# STM8L-FOX_80m_CNTL_V5_3.net
KiCad netlist of a schematic drawn in EAGLE
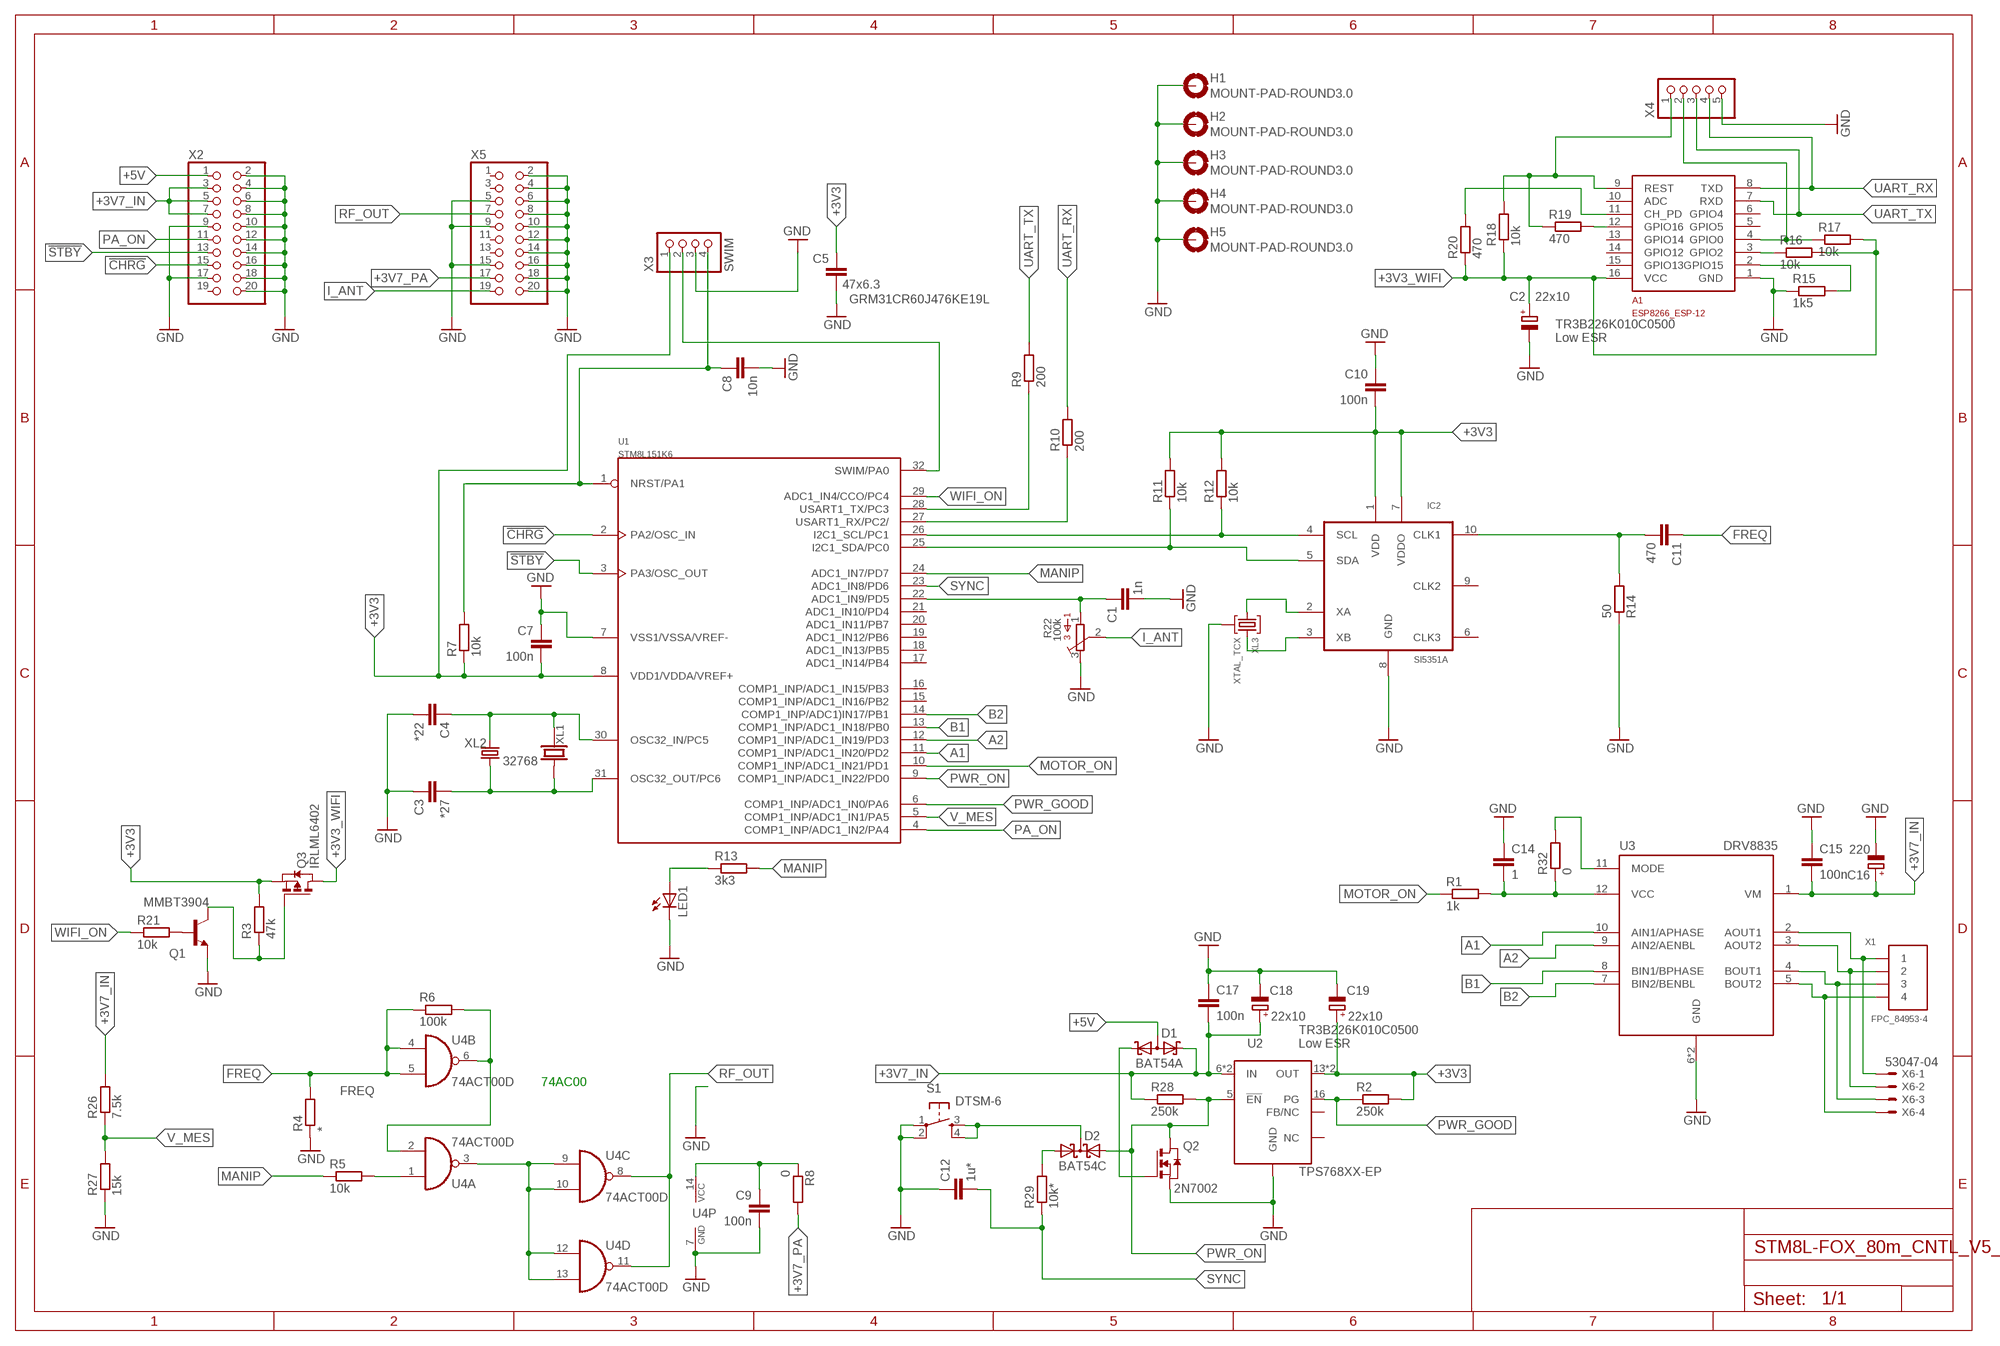
[diagram p0: schematic, sheet 1]

(export (version "E")
  (design (tool "Eeschema 10.0.6"))
  (components
    (comp (ref "A1")
      (value "ESP8266_ESP-12")
      (footprint "eagle-import:ESP8266-ESP12")
      (libsource (lib "eagle-import") (part "ESP8266_ESP-12"))
    )
    (comp (ref "C1")
      (value "1n")
      (footprint "eagle-import:C1206K")
      (libsource (lib "eagle-import") (part "C-EUC1206K"))
    )
    (comp (ref "C2")
      (value "22x10")
      (footprint "eagle-import:B_3528-21W")
      (libsource (lib "eagle-import") (part "CPOL-EUB/3528-21W"))
    )
    (comp (ref "C3")
      (value "*27")
      (footprint "eagle-import:C0805K")
      (libsource (lib "eagle-import") (part "C-EUC0805K"))
    )
    (comp (ref "C4")
      (value "*22")
      (footprint "eagle-import:C0805K")
      (libsource (lib "eagle-import") (part "C-EUC0805K"))
    )
    (comp (ref "C5")
      (value "47x6.3")
      (footprint "eagle-import:C1206K")
      (libsource (lib "eagle-import") (part "C-EUC1206K"))
    )
    (comp (ref "C7")
      (value "100n")
      (footprint "eagle-import:C1206K")
      (libsource (lib "eagle-import") (part "C-EUC1206K"))
    )
    (comp (ref "C8")
      (value "10n")
      (footprint "eagle-import:C0805K")
      (libsource (lib "eagle-import") (part "C-EUC0805K"))
    )
    (comp (ref "C9")
      (value "100n")
      (footprint "eagle-import:C1206K")
      (libsource (lib "eagle-import") (part "C-EUC1206K"))
    )
    (comp (ref "C10")
      (value "100n")
      (footprint "eagle-import:C1206K")
      (libsource (lib "eagle-import") (part "C-EUC1206K"))
    )
    (comp (ref "C11")
      (value "470")
      (footprint "eagle-import:C1206K")
      (libsource (lib "eagle-import") (part "C-EUC1206K"))
    )
    (comp (ref "C12")
      (value "1u*")
      (footprint "eagle-import:C1206K")
      (libsource (lib "eagle-import") (part "C-EUC1206K"))
    )
    (comp (ref "C14")
      (value "1")
      (footprint "eagle-import:C1206K")
      (libsource (lib "eagle-import") (part "C-EUC1206K"))
    )
    (comp (ref "C15")
      (value "100n")
      (footprint "eagle-import:C1206K")
      (libsource (lib "eagle-import") (part "C-EUC1206K"))
    )
    (comp (ref "C16")
      (value "220")
      (footprint "eagle-import:C_6032-28R")
      (libsource (lib "eagle-import") (part "CPOL-EUC/6032-28R"))
    )
    (comp (ref "C17")
      (value "100n")
      (footprint "eagle-import:C1206K")
      (libsource (lib "eagle-import") (part "C-EUC1206K"))
    )
    (comp (ref "C18")
      (value "22x10")
      (footprint "eagle-import:B_3528-21W")
      (libsource (lib "eagle-import") (part "CPOL-EUB/3528-21W"))
    )
    (comp (ref "C19")
      (value "22x10")
      (footprint "eagle-import:B_3528-21W")
      (libsource (lib "eagle-import") (part "CPOL-EUB/3528-21W"))
    )
    (comp (ref "D1")
      (value "BAT54A")
      (footprint "eagle-import:SOT23")
      (libsource (lib "eagle-import") (part "BAT54A"))
    )
    (comp (ref "D2")
      (value "BAT54C")
      (footprint "eagle-import:SOT23")
      (libsource (lib "eagle-import") (part "BAT54C"))
    )
    (comp (ref "H1")
      (value "MOUNT-PAD-ROUND3.0")
      (footprint "eagle-import:3,0-PAD")
      (libsource (lib "eagle-import") (part "MOUNT-PAD-ROUND3.0"))
    )
    (comp (ref "H2")
      (value "MOUNT-PAD-ROUND3.0")
      (footprint "eagle-import:3,0-PAD")
      (libsource (lib "eagle-import") (part "MOUNT-PAD-ROUND3.0"))
    )
    (comp (ref "H3")
      (value "MOUNT-PAD-ROUND3.0")
      (footprint "eagle-import:3,0-PAD")
      (libsource (lib "eagle-import") (part "MOUNT-PAD-ROUND3.0"))
    )
    (comp (ref "H4")
      (value "MOUNT-PAD-ROUND3.0")
      (footprint "eagle-import:3,0-PAD")
      (libsource (lib "eagle-import") (part "MOUNT-PAD-ROUND3.0"))
    )
    (comp (ref "H5")
      (value "MOUNT-PAD-ROUND3.0")
      (footprint "eagle-import:3,0-PAD")
      (libsource (lib "eagle-import") (part "MOUNT-PAD-ROUND3.0"))
    )
    (comp (ref "IC2")
      (value "SI5351A")
      (footprint "eagle-import:MSOP10")
      (libsource (lib "eagle-import") (part "SI5351A"))
    )
    (comp (ref "LED1")
      (value "LED3MM")
      (footprint "eagle-import:LED3MM")
      (libsource (lib "eagle-import") (part "LED3MM"))
    )
    (comp (ref "Q1")
      (value "MMBT3904")
      (footprint "eagle-import:SOT23-BEC")
      (libsource (lib "eagle-import") (part "-NPN-SOT23-BECMMBT3904LT1"))
    )
    (comp (ref "Q2")
      (value "2N7002")
      (footprint "eagle-import:SOT-23")
      (libsource (lib "eagle-import") (part "NMOSSOT23"))
    )
    (comp (ref "Q3")
      (value "IRLML6402")
      (footprint "eagle-import:SOT-23")
      (libsource (lib "eagle-import") (part "IRLML6402"))
    )
    (comp (ref "R1")
      (value "1k")
      (footprint "eagle-import:R1206")
      (libsource (lib "eagle-import") (part "R-EU_R1206"))
    )
    (comp (ref "R2")
      (value "250k")
      (footprint "eagle-import:R1206")
      (libsource (lib "eagle-import") (part "R-EU_R1206"))
    )
    (comp (ref "R3")
      (value "47k")
      (footprint "eagle-import:R1206")
      (libsource (lib "eagle-import") (part "R-EU_R1206"))
    )
    (comp (ref "R4")
      (value "*")
      (footprint "eagle-import:R1206")
      (libsource (lib "eagle-import") (part "R-EU_R1206"))
    )
    (comp (ref "R5")
      (value "10k")
      (footprint "eagle-import:R1206")
      (libsource (lib "eagle-import") (part "R-EU_R1206"))
    )
    (comp (ref "R6")
      (value "100k")
      (footprint "eagle-import:R1206")
      (libsource (lib "eagle-import") (part "R-EU_R1206"))
    )
    (comp (ref "R7")
      (value "10k")
      (footprint "eagle-import:R1206")
      (libsource (lib "eagle-import") (part "R-EU_R1206"))
    )
    (comp (ref "R8")
      (value "0")
      (footprint "eagle-import:R1206")
      (libsource (lib "eagle-import") (part "R-EU_R1206"))
    )
    (comp (ref "R9")
      (value "200")
      (footprint "eagle-import:R1206")
      (libsource (lib "eagle-import") (part "R-EU_R1206"))
    )
    (comp (ref "R10")
      (value "200")
      (footprint "eagle-import:R1206")
      (libsource (lib "eagle-import") (part "R-EU_R1206"))
    )
    (comp (ref "R11")
      (value "10k")
      (footprint "eagle-import:R1206")
      (libsource (lib "eagle-import") (part "R-EU_R1206"))
    )
    (comp (ref "R12")
      (value "10k")
      (footprint "eagle-import:R1206")
      (libsource (lib "eagle-import") (part "R-EU_R1206"))
    )
    (comp (ref "R13")
      (value "3k3")
      (footprint "eagle-import:R1206")
      (libsource (lib "eagle-import") (part "R-EU_R1206"))
    )
    (comp (ref "R14")
      (value "50")
      (footprint "eagle-import:R1206")
      (libsource (lib "eagle-import") (part "R-EU_R1206"))
    )
    (comp (ref "R15")
      (value "1k5")
      (footprint "eagle-import:R1206")
      (libsource (lib "eagle-import") (part "R-EU_R1206"))
    )
    (comp (ref "R16")
      (value "10k")
      (footprint "eagle-import:R1206")
      (libsource (lib "eagle-import") (part "R-EU_R1206"))
    )
    (comp (ref "R17")
      (value "10k")
      (footprint "eagle-import:R1206")
      (libsource (lib "eagle-import") (part "R-EU_R1206"))
    )
    (comp (ref "R18")
      (value "10k")
      (footprint "eagle-import:R1206")
      (libsource (lib "eagle-import") (part "R-EU_R1206"))
    )
    (comp (ref "R19")
      (value "470")
      (footprint "eagle-import:R1206")
      (libsource (lib "eagle-import") (part "R-EU_R1206"))
    )
    (comp (ref "R20")
      (value "470")
      (footprint "eagle-import:R1206")
      (libsource (lib "eagle-import") (part "R-EU_R1206"))
    )
    (comp (ref "R21")
      (value "10k")
      (footprint "eagle-import:R1206")
      (libsource (lib "eagle-import") (part "R-EU_R1206"))
    )
    (comp (ref "R22")
      (value "100k")
      (footprint "eagle-import:3362R")
      (libsource (lib "eagle-import") (part "3362R"))
    )
    (comp (ref "R26")
      (value "7.5k")
      (footprint "eagle-import:R1206")
      (libsource (lib "eagle-import") (part "R-EU_R1206"))
    )
    (comp (ref "R27")
      (value "15k")
      (footprint "eagle-import:R1206")
      (libsource (lib "eagle-import") (part "R-EU_R1206"))
    )
    (comp (ref "R28")
      (value "250k")
      (footprint "eagle-import:R1206")
      (libsource (lib "eagle-import") (part "R-EU_R1206"))
    )
    (comp (ref "R29")
      (value "10k*")
      (footprint "eagle-import:R1206")
      (libsource (lib "eagle-import") (part "R-EU_R1206"))
    )
    (comp (ref "R32")
      (value "0")
      (footprint "eagle-import:R1206")
      (libsource (lib "eagle-import") (part "R-EU_R1206"))
    )
    (comp (ref "S1")
      (value "DTSM-6")
      (footprint "eagle-import:DTSM-6")
      (libsource (lib "eagle-import") (part "DTSM-6"))
    )
    (comp (ref "U1")
      (value "STM8L151K6")
      (footprint "eagle-import:LQFP32-7X7")
      (libsource (lib "eagle-import") (part "STM8L151K6"))
    )
    (comp (ref "U2")
      (value "TPS768XX-EP")
      (footprint "eagle-import:TSSOP-20-PWP")
      (libsource (lib "eagle-import") (part "TPS768XX-EP"))
    )
    (comp (ref "U3")
      (value "DRV8835")
      (footprint "eagle-import:WSON_2X3")
      (libsource (lib "eagle-import") (part "DRV8835"))
    )
    (comp (ref "U4")
      (value "74ACT00D")
      (footprint "eagle-import:SO14")
      (libsource (lib "eagle-import") (part "7400DACT"))
    )
    (comp (ref "X1")
      (value "FPC_84953-4")
      (footprint "eagle-import:FPC_84953-4")
      (libsource (lib "eagle-import") (part "FPC_84953-4"))
    )
    (comp (ref "X2")
      (value "PINHD-2X10")
      (footprint "eagle-import:2X10")
      (libsource (lib "eagle-import") (part "PINHD-2X10"))
    )
    (comp (ref "X3")
      (value "SWIM")
      (footprint "eagle-import:1X04")
      (libsource (lib "eagle-import") (part "PINHD-1X4"))
    )
    (comp (ref "X4")
      (value "PINHD-1X5")
      (footprint "eagle-import:1X05")
      (libsource (lib "eagle-import") (part "PINHD-1X5"))
    )
    (comp (ref "X5")
      (value "PINHD-2X10")
      (footprint "eagle-import:2X10")
      (libsource (lib "eagle-import") (part "PINHD-2X10"))
    )
    (comp (ref "X6")
      (value "53047-04")
      (footprint "eagle-import:53047-04")
      (fields (field (name "MF") "WALDOM/MOLEX") (field (name "MPN") "53047-0410"))
      (libsource (lib "eagle-import") (part "53?-04047"))
    )
    (comp (ref "XL1")
      (value "CRYSTALSMD")
      (footprint "eagle-import:EPSON-MC146")
      (libsource (lib "eagle-import") (part "CRYSTALSMD"))
    )
    (comp (ref "XL2")
      (value "32768")
      (footprint "eagle-import:TC38H-PCB")
      (libsource (lib "eagle-import") (part "CRYSTALTC38H-PCB"))
    )
    (comp (ref "XL3")
      (value "XTAL_TCX")
      (footprint "eagle-import:TXC")
      (libsource (lib "eagle-import") (part "XTAL_TCX"))
    )
  )
  (nets
    (net (code "1") (name "+3V3") (class "Default")
      (node (ref "C10") (pin "1") (pinfunction "1_1") (pintype "passive"))
      (node (ref "C19") (pin "+") (pinfunction "+_+") (pintype "passive"))
      (node (ref "C5") (pin "2") (pinfunction "2_2") (pintype "passive"))
      (node (ref "C7") (pin "1") (pinfunction "1_1") (pintype "passive"))
      (node (ref "IC2") (pin "1") (pinfunction "VDD_1") (pintype "bidirectional"))
      (node (ref "IC2") (pin "7") (pinfunction "VDDO_7") (pintype "bidirectional"))
      (node (ref "Q3") (pin "2") (pinfunction "S_2") (pintype "passive"))
      (node (ref "R11") (pin "2") (pinfunction "2_2") (pintype "passive"))
      (node (ref "R12") (pin "2") (pinfunction "2_2") (pintype "passive"))
      (node (ref "R2") (pin "2") (pinfunction "2_2") (pintype "passive"))
      (node (ref "R3") (pin "2") (pinfunction "2_2") (pintype "passive"))
      (node (ref "R7") (pin "1") (pinfunction "1_1") (pintype "passive"))
      (node (ref "U1") (pin "8") (pinfunction "VDD1/VDDA/VREF+_8") (pintype "bidirectional"))
      (node (ref "U2") (pin "13") (pinfunction "OUT_13") (pintype "output"))
      (node (ref "U2") (pin "14") (pinfunction "OUT_14") (pintype "output"))
      (node (ref "X3") (pin "1") (pinfunction "1_1") (pintype "passive"))
    )
    (net (code "2") (name "+3V3_WIFI") (class "Default")
      (node (ref "A1") (pin "16") (pinfunction "VCC_16") (pintype "bidirectional"))
      (node (ref "C2") (pin "+") (pinfunction "+_+") (pintype "passive"))
      (node (ref "Q3") (pin "3") (pinfunction "D_3") (pintype "passive"))
      (node (ref "R16") (pin "2") (pinfunction "2_2") (pintype "passive"))
      (node (ref "R17") (pin "2") (pinfunction "2_2") (pintype "passive"))
      (node (ref "R18") (pin "1") (pinfunction "1_1") (pintype "passive"))
      (node (ref "R20") (pin "1") (pinfunction "1_1") (pintype "passive"))
    )
    (net (code "3") (name "+3V7_IN") (class "Default")
      (node (ref "C15") (pin "2") (pinfunction "2_2") (pintype "passive"))
      (node (ref "C16") (pin "+") (pinfunction "+_+") (pintype "passive"))
      (node (ref "C17") (pin "2") (pinfunction "2_2") (pintype "passive"))
      (node (ref "C18") (pin "+") (pinfunction "+_+") (pintype "passive"))
      (node (ref "D1") (pin "2") (pinfunction "K2_2") (pintype "passive"))
      (node (ref "R26") (pin "2") (pinfunction "2_2") (pintype "passive"))
      (node (ref "R28") (pin "1") (pinfunction "1_1") (pintype "passive"))
      (node (ref "U2") (pin "6") (pinfunction "IN_6") (pintype "input"))
      (node (ref "U2") (pin "7") (pinfunction "IN_7") (pintype "input"))
      (node (ref "U3") (pin "1") (pinfunction "VM_1") (pintype "bidirectional"))
      (node (ref "X2") (pin "3") (pinfunction "3_3") (pintype "passive"))
      (node (ref "X2") (pin "5") (pinfunction "5_5") (pintype "passive"))
      (node (ref "X2") (pin "7") (pinfunction "7_7") (pintype "passive"))
    )
    (net (code "4") (name "+3V7_PA") (class "Default")
      (node (ref "R8") (pin "2") (pinfunction "2_2") (pintype "passive"))
      (node (ref "X5") (pin "17") (pinfunction "17_17") (pintype "passive"))
    )
    (net (code "5") (name "+5V") (class "Default")
      (node (ref "D1") (pin "3") (pinfunction "AA_3") (pintype "passive"))
      (node (ref "X2") (pin "1") (pinfunction "1_1") (pintype "passive"))
    )
    (net (code "6") (name "/~{CHRG}") (class "Default")
      (node (ref "U1") (pin "2") (pinfunction "PA2/OSC_IN_2") (pintype "bidirectional"))
      (node (ref "X2") (pin "15") (pinfunction "15_15") (pintype "passive"))
    )
    (net (code "7") (name "/~{STBY}") (class "Default")
      (node (ref "U1") (pin "3") (pinfunction "PA3/OSC_OUT_3") (pintype "bidirectional"))
      (node (ref "X2") (pin "13") (pinfunction "13_13") (pintype "passive"))
    )
    (net (code "8") (name "A1") (class "Default")
      (node (ref "U1") (pin "11") (pinfunction "COMP1_INP/ADC1_IN20/PD2_11") (pintype "bidirectional"))
      (node (ref "U3") (pin "10") (pinfunction "AIN1/APHASE_10") (pintype "bidirectional"))
    )
    (net (code "9") (name "A2") (class "Default")
      (node (ref "U1") (pin "12") (pinfunction "COMP1_INP/ADC1_IN19/PD3_12") (pintype "bidirectional"))
      (node (ref "U3") (pin "9") (pinfunction "AIN2/AENBL_9") (pintype "bidirectional"))
    )
    (net (code "10") (name "B1") (class "Default")
      (node (ref "U1") (pin "13") (pinfunction "COMP1_INP/ADC1_IN18/PB0_13") (pintype "bidirectional"))
      (node (ref "U3") (pin "8") (pinfunction "BIN1/BPHASE_8") (pintype "bidirectional"))
    )
    (net (code "11") (name "B2") (class "Default")
      (node (ref "U1") (pin "14") (pinfunction "COMP1_INP/ADC1)IN17/PB1_14") (pintype "bidirectional"))
      (node (ref "U3") (pin "7") (pinfunction "BIN2/BENBL_7") (pintype "bidirectional"))
    )
    (net (code "12") (name "FREQ") (class "Default")
      (node (ref "C11") (pin "1") (pinfunction "1_1") (pintype "passive"))
      (node (ref "R4") (pin "2") (pinfunction "2_2") (pintype "passive"))
      (node (ref "R6") (pin "1") (pinfunction "1_1") (pintype "passive"))
      (node (ref "U4") (pin "4") (pinfunction "I0_4") (pintype "input"))
      (node (ref "U4") (pin "5") (pinfunction "I1_5") (pintype "input"))
    )
    (net (code "13") (name "GND") (class "Default")
      (node (ref "A1") (pin "1") (pinfunction "GND_1") (pintype "bidirectional"))
      (node (ref "C1") (pin "1") (pinfunction "1_1") (pintype "passive"))
      (node (ref "C10") (pin "2") (pinfunction "2_2") (pintype "passive"))
      (node (ref "C12") (pin "1") (pinfunction "1_1") (pintype "passive"))
      (node (ref "C14") (pin "1") (pinfunction "1_1") (pintype "passive"))
      (node (ref "C15") (pin "1") (pinfunction "1_1") (pintype "passive"))
      (node (ref "C16") (pin "-") (pinfunction "-_-") (pintype "passive"))
      (node (ref "C17") (pin "1") (pinfunction "1_1") (pintype "passive"))
      (node (ref "C18") (pin "-") (pinfunction "-_-") (pintype "passive"))
      (node (ref "C19") (pin "-") (pinfunction "-_-") (pintype "passive"))
      (node (ref "C2") (pin "-") (pinfunction "-_-") (pintype "passive"))
      (node (ref "C3") (pin "1") (pinfunction "1_1") (pintype "passive"))
      (node (ref "C4") (pin "2") (pinfunction "2_2") (pintype "passive"))
      (node (ref "C5") (pin "1") (pinfunction "1_1") (pintype "passive"))
      (node (ref "C7") (pin "2") (pinfunction "2_2") (pintype "passive"))
      (node (ref "C8") (pin "2") (pinfunction "2_2") (pintype "passive"))
      (node (ref "C9") (pin "2") (pinfunction "2_2") (pintype "passive"))
      (node (ref "H1") (pin "B3,0") (pinfunction "MOUNT_B3,0") (pintype "passive"))
      (node (ref "H2") (pin "B3,0") (pinfunction "MOUNT_B3,0") (pintype "passive"))
      (node (ref "H3") (pin "B3,0") (pinfunction "MOUNT_B3,0") (pintype "passive"))
      (node (ref "H4") (pin "B3,0") (pinfunction "MOUNT_B3,0") (pintype "passive"))
      (node (ref "H5") (pin "B3,0") (pinfunction "MOUNT_B3,0") (pintype "passive"))
      (node (ref "IC2") (pin "8") (pinfunction "GND_8") (pintype "bidirectional"))
      (node (ref "LED1") (pin "K") (pinfunction "C_K") (pintype "passive"))
      (node (ref "Q1") (pin "E") (pinfunction "E_E") (pintype "passive"))
      (node (ref "Q2") (pin "2") (pinfunction "S_2") (pintype "passive"))
      (node (ref "R14") (pin "1") (pinfunction "1_1") (pintype "passive"))
      (node (ref "R15") (pin "1") (pinfunction "1_1") (pintype "passive"))
      (node (ref "R22") (pin "3") (pinfunction "3_3") (pintype "passive"))
      (node (ref "R27") (pin "1") (pinfunction "1_1") (pintype "passive"))
      (node (ref "R4") (pin "1") (pinfunction "1_1") (pintype "passive"))
      (node (ref "S1") (pin "1") (pinfunction "1_1") (pintype "passive"))
      (node (ref "S1") (pin "2") (pinfunction "2_2") (pintype "passive"))
      (node (ref "U1") (pin "7") (pinfunction "VSS1/VSSA/VREF-_7") (pintype "bidirectional"))
      (node (ref "U2") (pin "1") (pinfunction "GND_1") (pintype "bidirectional"))
      (node (ref "U2") (pin "10") (pinfunction "GND_10") (pintype "bidirectional"))
      (node (ref "U2") (pin "11") (pinfunction "GND_11") (pintype "bidirectional"))
      (node (ref "U2") (pin "12") (pinfunction "GND_12") (pintype "bidirectional"))
      (node (ref "U2") (pin "19") (pinfunction "GND_19") (pintype "bidirectional"))
      (node (ref "U2") (pin "2") (pinfunction "GND_2") (pintype "bidirectional"))
      (node (ref "U2") (pin "20") (pinfunction "GND_20") (pintype "bidirectional"))
      (node (ref "U2") (pin "3") (pinfunction "GND_3") (pintype "bidirectional"))
      (node (ref "U2") (pin "9") (pinfunction "GND_9") (pintype "bidirectional"))
      (node (ref "U2") (pin "PAD") (pinfunction "GND_PAD") (pintype "bidirectional"))
      (node (ref "U3") (pin "6") (pinfunction "GND_6") (pintype "bidirectional"))
      (node (ref "U3") (pin "PAD") (pinfunction "GND_PAD") (pintype "bidirectional"))
      (node (ref "U4") (pin "7") (pinfunction "GND_7") (pintype "power_in"))
      (node (ref "X2") (pin "10") (pinfunction "10_10") (pintype "passive"))
      (node (ref "X2") (pin "12") (pinfunction "12_12") (pintype "passive"))
      (node (ref "X2") (pin "14") (pinfunction "14_14") (pintype "passive"))
      (node (ref "X2") (pin "16") (pinfunction "16_16") (pintype "passive"))
      (node (ref "X2") (pin "17") (pinfunction "17_17") (pintype "passive"))
      (node (ref "X2") (pin "18") (pinfunction "18_18") (pintype "passive"))
      (node (ref "X2") (pin "2") (pinfunction "2_2") (pintype "passive"))
      (node (ref "X2") (pin "20") (pinfunction "20_20") (pintype "passive"))
      (node (ref "X2") (pin "4") (pinfunction "4_4") (pintype "passive"))
      (node (ref "X2") (pin "6") (pinfunction "6_6") (pintype "passive"))
      (node (ref "X2") (pin "8") (pinfunction "8_8") (pintype "passive"))
      (node (ref "X2") (pin "9") (pinfunction "9_9") (pintype "passive"))
      (node (ref "X3") (pin "3") (pinfunction "3_3") (pintype "passive"))
      (node (ref "X4") (pin "5") (pinfunction "5_5") (pintype "passive"))
      (node (ref "X5") (pin "10") (pinfunction "10_10") (pintype "passive"))
      (node (ref "X5") (pin "12") (pinfunction "12_12") (pintype "passive"))
      (node (ref "X5") (pin "14") (pinfunction "14_14") (pintype "passive"))
      (node (ref "X5") (pin "15") (pinfunction "15_15") (pintype "passive"))
      (node (ref "X5") (pin "16") (pinfunction "16_16") (pintype "passive"))
      (node (ref "X5") (pin "18") (pinfunction "18_18") (pintype "passive"))
      (node (ref "X5") (pin "2") (pinfunction "2_2") (pintype "passive"))
      (node (ref "X5") (pin "20") (pinfunction "20_20") (pintype "passive"))
      (node (ref "X5") (pin "4") (pinfunction "4_4") (pintype "passive"))
      (node (ref "X5") (pin "5") (pinfunction "5_5") (pintype "passive"))
      (node (ref "X5") (pin "6") (pinfunction "6_6") (pintype "passive"))
      (node (ref "X5") (pin "8") (pinfunction "8_8") (pintype "passive"))
      (node (ref "X5") (pin "9") (pinfunction "9_9") (pintype "passive"))
      (node (ref "XL3") (pin "2") (pinfunction "2_2") (pintype "passive"))
      (node (ref "XL3") (pin "4") (pinfunction "2_4") (pintype "passive"))
    )
    (net (code "14") (name "I_ANT") (class "Default")
      (node (ref "R22") (pin "2") (pinfunction "2_2") (pintype "passive"))
      (node (ref "X5") (pin "19") (pinfunction "19_19") (pintype "passive"))
    )
    (net (code "15") (name "MANIP") (class "Default")
      (node (ref "R13") (pin "2") (pinfunction "2_2") (pintype "passive"))
      (node (ref "R5") (pin "1") (pinfunction "1_1") (pintype "passive"))
      (node (ref "U1") (pin "24") (pinfunction "ADC1_IN7/PD7_24") (pintype "bidirectional"))
    )
    (net (code "16") (name "MOTOR_ON") (class "Default")
      (node (ref "R1") (pin "1") (pinfunction "1_1") (pintype "passive"))
      (node (ref "U1") (pin "10") (pinfunction "COMP1_INP/ADC1_IN21/PD1_10") (pintype "bidirectional"))
    )
    (net (code "17") (name "Net-(A1-CH_PD)") (class "Default")
      (node (ref "A1") (pin "11") (pinfunction "CH_PD_11") (pintype "bidirectional"))
      (node (ref "R20") (pin "2") (pinfunction "2_2") (pintype "passive"))
    )
    (net (code "18") (name "Net-(A1-GPIO0)") (class "Default")
      (node (ref "A1") (pin "4") (pinfunction "GPIO0_4") (pintype "bidirectional"))
      (node (ref "R17") (pin "1") (pinfunction "1_1") (pintype "passive"))
      (node (ref "X4") (pin "2") (pinfunction "2_2") (pintype "passive"))
    )
    (net (code "19") (name "Net-(A1-GPIO2)") (class "Default")
      (node (ref "A1") (pin "3") (pinfunction "GPIO2_3") (pintype "bidirectional"))
      (node (ref "R16") (pin "1") (pinfunction "1_1") (pintype "passive"))
    )
    (net (code "20") (name "Net-(A1-GPIO15)") (class "Default")
      (node (ref "A1") (pin "2") (pinfunction "GPIO15_2") (pintype "bidirectional"))
      (node (ref "R15") (pin "2") (pinfunction "2_2") (pintype "passive"))
    )
    (net (code "21") (name "Net-(A1-GPIO16)") (class "Default")
      (node (ref "A1") (pin "12") (pinfunction "GPIO16_12") (pintype "bidirectional"))
      (node (ref "R19") (pin "2") (pinfunction "2_2") (pintype "passive"))
    )
    (net (code "22") (name "Net-(A1-REST)") (class "Default")
      (node (ref "A1") (pin "9") (pinfunction "REST_9") (pintype "bidirectional"))
      (node (ref "R18") (pin "2") (pinfunction "2_2") (pintype "passive"))
      (node (ref "R19") (pin "1") (pinfunction "1_1") (pintype "passive"))
      (node (ref "X4") (pin "1") (pinfunction "1_1") (pintype "passive"))
    )
    (net (code "23") (name "Net-(D1-K1)") (class "Default")
      (node (ref "D1") (pin "1") (pinfunction "K1_1") (pintype "passive"))
      (node (ref "Q2") (pin "3") (pinfunction "G_3") (pintype "passive"))
    )
    (net (code "24") (name "Net-(D2-A1)") (class "Default")
      (node (ref "D2") (pin "1") (pinfunction "A1_1") (pintype "passive"))
      (node (ref "R29") (pin "2") (pinfunction "2_2") (pintype "passive"))
    )
    (net (code "25") (name "Net-(D2-CC)") (class "Default")
      (node (ref "D2") (pin "3") (pinfunction "CC_3") (pintype "passive"))
      (node (ref "S1") (pin "3") (pinfunction "3_3") (pintype "passive"))
      (node (ref "S1") (pin "4") (pinfunction "4_4") (pintype "passive"))
    )
    (net (code "26") (name "Net-(IC2-CLK1)") (class "Default")
      (node (ref "C11") (pin "2") (pinfunction "2_2") (pintype "passive"))
      (node (ref "IC2") (pin "10") (pinfunction "CLK1_10") (pintype "bidirectional"))
      (node (ref "R14") (pin "2") (pinfunction "2_2") (pintype "passive"))
    )
    (net (code "27") (name "Net-(IC2-SCL)") (class "Default")
      (node (ref "IC2") (pin "4") (pinfunction "SCL_4") (pintype "bidirectional"))
      (node (ref "R12") (pin "1") (pinfunction "1_1") (pintype "passive"))
      (node (ref "U1") (pin "26") (pinfunction "I2C1_SCL/PC1_26") (pintype "bidirectional"))
    )
    (net (code "28") (name "Net-(IC2-SDA)") (class "Default")
      (node (ref "IC2") (pin "5") (pinfunction "SDA_5") (pintype "bidirectional"))
      (node (ref "R11") (pin "1") (pinfunction "1_1") (pintype "passive"))
      (node (ref "U1") (pin "25") (pinfunction "I2C1_SDA/PC0_25") (pintype "bidirectional"))
    )
    (net (code "29") (name "Net-(IC2-XA)") (class "Default")
      (node (ref "IC2") (pin "2") (pinfunction "XA_2") (pintype "bidirectional"))
      (node (ref "XL3") (pin "1") (pinfunction "1_1") (pintype "passive"))
    )
    (net (code "30") (name "Net-(IC2-XB)") (class "Default")
      (node (ref "IC2") (pin "3") (pinfunction "XB_3") (pintype "bidirectional"))
      (node (ref "XL3") (pin "3") (pinfunction "3_3") (pintype "passive"))
    )
    (net (code "31") (name "Net-(LED1-PadA)") (class "Default")
      (node (ref "LED1") (pin "A") (pinfunction "A_A") (pintype "passive"))
      (node (ref "R13") (pin "1") (pinfunction "1_1") (pintype "passive"))
    )
    (net (code "32") (name "Net-(Q1-PadB)") (class "Default")
      (node (ref "Q1") (pin "B") (pinfunction "B_B") (pintype "passive"))
      (node (ref "R21") (pin "2") (pinfunction "2_2") (pintype "passive"))
    )
    (net (code "33") (name "Net-(Q3-G)") (class "Default")
      (node (ref "Q1") (pin "C") (pinfunction "C_C") (pintype "passive"))
      (node (ref "Q3") (pin "1") (pinfunction "G_1") (pintype "passive"))
      (node (ref "R3") (pin "1") (pinfunction "1_1") (pintype "passive"))
    )
    (net (code "34") (name "Net-(U1-ADC1_IN9{slash}PD5)") (class "Default")
      (node (ref "C1") (pin "2") (pinfunction "2_2") (pintype "passive"))
      (node (ref "R22") (pin "1") (pinfunction "1_1") (pintype "passive"))
      (node (ref "U1") (pin "22") (pinfunction "ADC1_IN9/PD5_22") (pintype "bidirectional"))
    )
    (net (code "35") (name "Net-(U1-NRST{slash}PA1)") (class "Default")
      (node (ref "C8") (pin "1") (pinfunction "1_1") (pintype "passive"))
      (node (ref "R7") (pin "2") (pinfunction "2_2") (pintype "passive"))
      (node (ref "U1") (pin "1") (pinfunction "NRST/PA1_1") (pintype "bidirectional"))
      (node (ref "X3") (pin "4") (pinfunction "4_4") (pintype "passive"))
    )
    (net (code "36") (name "Net-(U1-OSC32_IN{slash}PC5)") (class "Default")
      (node (ref "C4") (pin "1") (pinfunction "1_1") (pintype "passive"))
      (node (ref "U1") (pin "30") (pinfunction "OSC32_IN/PC5_30") (pintype "bidirectional"))
      (node (ref "XL1") (pin "P$1") (pinfunction "1_P$1") (pintype "passive"))
      (node (ref "XL2") (pin "P$2") (pinfunction "2_P$2") (pintype "passive"))
    )
    (net (code "37") (name "Net-(U1-OSC32_OUT{slash}PC6)") (class "Default")
      (node (ref "C3") (pin "2") (pinfunction "2_2") (pintype "passive"))
      (node (ref "U1") (pin "31") (pinfunction "OSC32_OUT/PC6_31") (pintype "bidirectional"))
      (node (ref "XL1") (pin "P$2") (pinfunction "2_P$2") (pintype "passive"))
      (node (ref "XL2") (pin "P$1") (pinfunction "1_P$1") (pintype "passive"))
    )
    (net (code "38") (name "Net-(U1-SWIM{slash}PA0)") (class "Default")
      (node (ref "U1") (pin "32") (pinfunction "SWIM/PA0_32") (pintype "bidirectional"))
      (node (ref "X3") (pin "2") (pinfunction "2_2") (pintype "passive"))
    )
    (net (code "39") (name "Net-(U1-USART1_RX{slash}PC2{slash})") (class "Default")
      (node (ref "R10") (pin "1") (pinfunction "1_1") (pintype "passive"))
      (node (ref "U1") (pin "27") (pinfunction "USART1_RX/PC2/_27") (pintype "bidirectional"))
    )
    (net (code "40") (name "Net-(U1-USART1_TX{slash}PC3)") (class "Default")
      (node (ref "R9") (pin "1") (pinfunction "1_1") (pintype "passive"))
      (node (ref "U1") (pin "28") (pinfunction "USART1_TX/PC3_28") (pintype "bidirectional"))
    )
    (net (code "41") (name "Net-(U3-AOUT1)") (class "Default")
      (node (ref "U3") (pin "2") (pinfunction "AOUT1_2") (pintype "bidirectional"))
      (node (ref "X1") (pin "1") (pinfunction "1_1") (pintype "bidirectional"))
      (node (ref "X6") (pin "1") (pinfunction "S_1") (pintype "passive"))
    )
    (net (code "42") (name "Net-(U3-AOUT2)") (class "Default")
      (node (ref "U3") (pin "3") (pinfunction "AOUT2_3") (pintype "bidirectional"))
      (node (ref "X1") (pin "2") (pinfunction "2_2") (pintype "bidirectional"))
      (node (ref "X6") (pin "2") (pinfunction "S_2") (pintype "passive"))
    )
    (net (code "43") (name "Net-(U3-BOUT1)") (class "Default")
      (node (ref "U3") (pin "4") (pinfunction "BOUT1_4") (pintype "bidirectional"))
      (node (ref "X1") (pin "3") (pinfunction "3_3") (pintype "bidirectional"))
      (node (ref "X6") (pin "3") (pinfunction "S_3") (pintype "passive"))
    )
    (net (code "44") (name "Net-(U3-BOUT2)") (class "Default")
      (node (ref "U3") (pin "5") (pinfunction "BOUT2_5") (pintype "bidirectional"))
      (node (ref "X1") (pin "4") (pinfunction "4_4") (pintype "bidirectional"))
      (node (ref "X6") (pin "4") (pinfunction "S_4") (pintype "passive"))
    )
    (net (code "45") (name "Net-(U3-MODE)") (class "Default")
      (node (ref "R32") (pin "2") (pinfunction "2_2") (pintype "passive"))
      (node (ref "U3") (pin "11") (pinfunction "MODE_11") (pintype "bidirectional"))
    )
    (net (code "46") (name "Net-(U3-VCC)") (class "Default")
      (node (ref "C14") (pin "2") (pinfunction "2_2") (pintype "passive"))
      (node (ref "R1") (pin "2") (pinfunction "2_2") (pintype "passive"))
      (node (ref "R32") (pin "1") (pinfunction "1_1") (pintype "passive"))
      (node (ref "U3") (pin "12") (pinfunction "VCC_12") (pintype "bidirectional"))
    )
    (net (code "47") (name "Net-(U4A-I0)") (class "Default")
      (node (ref "R5") (pin "2") (pinfunction "2_2") (pintype "passive"))
      (node (ref "U4") (pin "1") (pinfunction "I0_1") (pintype "input"))
    )
    (net (code "48") (name "Net-(U4A-I1)") (class "Default")
      (node (ref "R6") (pin "2") (pinfunction "2_2") (pintype "passive"))
      (node (ref "U4") (pin "2") (pinfunction "I1_2") (pintype "input"))
      (node (ref "U4") (pin "6") (pinfunction "O_6") (pintype "output"))
    )
    (net (code "49") (name "Net-(U4A-O)") (class "Default")
      (node (ref "U4") (pin "10") (pinfunction "I1_10") (pintype "input"))
      (node (ref "U4") (pin "12") (pinfunction "I0_12") (pintype "input"))
      (node (ref "U4") (pin "13") (pinfunction "I1_13") (pintype "input"))
      (node (ref "U4") (pin "3") (pinfunction "O_3") (pintype "output"))
      (node (ref "U4") (pin "9") (pinfunction "I0_9") (pintype "input"))
    )
    (net (code "50") (name "Net-(U4E-VCC)") (class "Default")
      (node (ref "C9") (pin "1") (pinfunction "1_1") (pintype "passive"))
      (node (ref "R8") (pin "1") (pinfunction "1_1") (pintype "passive"))
      (node (ref "U4") (pin "14") (pinfunction "VCC_14") (pintype "power_in"))
    )
    (net (code "51") (name "PA_ON") (class "Default")
      (node (ref "U1") (pin "4") (pinfunction "COMP1_INP/ADC1_IN2/PA4_4") (pintype "bidirectional"))
      (node (ref "X2") (pin "11") (pinfunction "11_11") (pintype "passive"))
    )
    (net (code "52") (name "PWR_GOOD") (class "Default")
      (node (ref "R2") (pin "1") (pinfunction "1_1") (pintype "passive"))
      (node (ref "U1") (pin "6") (pinfunction "COMP1_INP/ADC1_IN0/PA6_6") (pintype "bidirectional"))
      (node (ref "U2") (pin "16") (pinfunction "PG_16") (pintype "bidirectional"))
    )
    (net (code "53") (name "PWR_ON") (class "Default")
      (node (ref "D2") (pin "2") (pinfunction "A2_2") (pintype "passive"))
      (node (ref "Q2") (pin "1") (pinfunction "D_1") (pintype "passive"))
      (node (ref "R28") (pin "2") (pinfunction "2_2") (pintype "passive"))
      (node (ref "U1") (pin "9") (pinfunction "COMP1_INP/ADC1_IN22/PD0_9") (pintype "bidirectional"))
      (node (ref "U2") (pin "5") (pinfunction "~{EN}_5") (pintype "input"))
    )
    (net (code "54") (name "RF_OUT") (class "Default")
      (node (ref "U4") (pin "11") (pinfunction "O_11") (pintype "output"))
      (node (ref "U4") (pin "8") (pinfunction "O_8") (pintype "output"))
      (node (ref "X5") (pin "7") (pinfunction "7_7") (pintype "passive"))
    )
    (net (code "55") (name "SYNC") (class "Default")
      (node (ref "C12") (pin "2") (pinfunction "2_2") (pintype "passive"))
      (node (ref "R29") (pin "1") (pinfunction "1_1") (pintype "passive"))
      (node (ref "U1") (pin "23") (pinfunction "ADC1_IN8/PD6_23") (pintype "bidirectional"))
    )
    (net (code "56") (name "UART_RX") (class "Default")
      (node (ref "A1") (pin "8") (pinfunction "TXD_8") (pintype "bidirectional"))
      (node (ref "R10") (pin "2") (pinfunction "2_2") (pintype "passive"))
      (node (ref "X4") (pin "4") (pinfunction "4_4") (pintype "passive"))
    )
    (net (code "57") (name "UART_TX") (class "Default")
      (node (ref "A1") (pin "7") (pinfunction "RXD_7") (pintype "bidirectional"))
      (node (ref "R9") (pin "2") (pinfunction "2_2") (pintype "passive"))
      (node (ref "X4") (pin "3") (pinfunction "3_3") (pintype "passive"))
    )
    (net (code "58") (name "V_MES") (class "Default")
      (node (ref "R26") (pin "1") (pinfunction "1_1") (pintype "passive"))
      (node (ref "R27") (pin "2") (pinfunction "2_2") (pintype "passive"))
      (node (ref "U1") (pin "5") (pinfunction "COMP1_INP/ADC1_IN1/PA5_5") (pintype "bidirectional"))
    )
    (net (code "59") (name "WIFI_ON") (class "Default")
      (node (ref "R21") (pin "1") (pinfunction "1_1") (pintype "passive"))
      (node (ref "U1") (pin "29") (pinfunction "ADC1_IN4/CCO/PC4_29") (pintype "bidirectional"))
    )
    (net (code "60") (name "unconnected-(A1-ADC-Pad10)") (class "Default")
      (node (ref "A1") (pin "10") (pinfunction "ADC_10") (pintype "bidirectional"))
    )
    (net (code "61") (name "unconnected-(A1-GPIO4-Pad6)") (class "Default")
      (node (ref "A1") (pin "6") (pinfunction "GPIO4_6") (pintype "bidirectional"))
    )
    (net (code "62") (name "unconnected-(A1-GPIO5-Pad5)") (class "Default")
      (node (ref "A1") (pin "5") (pinfunction "GPIO5_5") (pintype "bidirectional"))
    )
    (net (code "63") (name "unconnected-(A1-GPIO12-Pad14)") (class "Default")
      (node (ref "A1") (pin "14") (pinfunction "GPIO12_14") (pintype "bidirectional"))
    )
    (net (code "64") (name "unconnected-(A1-GPIO13-Pad15)") (class "Default")
      (node (ref "A1") (pin "15") (pinfunction "GPIO13_15") (pintype "bidirectional"))
    )
    (net (code "65") (name "unconnected-(A1-GPIO14-Pad13)") (class "Default")
      (node (ref "A1") (pin "13") (pinfunction "GPIO14_13") (pintype "bidirectional"))
    )
    (net (code "66") (name "unconnected-(IC2-CLK2-Pad9)") (class "Default")
      (node (ref "IC2") (pin "9") (pinfunction "CLK2_9") (pintype "bidirectional"))
    )
    (net (code "67") (name "unconnected-(IC2-CLK3-Pad6)") (class "Default")
      (node (ref "IC2") (pin "6") (pinfunction "CLK3_6") (pintype "bidirectional"))
    )
    (net (code "68") (name "unconnected-(U1-ADC1_IN10{slash}PD4-Pad21)") (class "Default")
      (node (ref "U1") (pin "21") (pinfunction "ADC1_IN10/PD4_21") (pintype "bidirectional"))
    )
    (net (code "69") (name "unconnected-(U1-ADC1_IN11{slash}PB7-Pad20)") (class "Default")
      (node (ref "U1") (pin "20") (pinfunction "ADC1_IN11/PB7_20") (pintype "bidirectional"))
    )
    (net (code "70") (name "unconnected-(U1-ADC1_IN12{slash}PB6-Pad19)") (class "Default")
      (node (ref "U1") (pin "19") (pinfunction "ADC1_IN12/PB6_19") (pintype "bidirectional"))
    )
    (net (code "71") (name "unconnected-(U1-ADC1_IN13{slash}PB5-Pad18)") (class "Default")
      (node (ref "U1") (pin "18") (pinfunction "ADC1_IN13/PB5_18") (pintype "bidirectional"))
    )
    (net (code "72") (name "unconnected-(U1-ADC1_IN14{slash}PB4-Pad17)") (class "Default")
      (node (ref "U1") (pin "17") (pinfunction "ADC1_IN14/PB4_17") (pintype "bidirectional"))
    )
    (net (code "73") (name "unconnected-(U1-COMP1_INP{slash}ADC1_IN15{slash}PB3-Pad16)") (class "Default")
      (node (ref "U1") (pin "16") (pinfunction "COMP1_INP/ADC1_IN15/PB3_16") (pintype "bidirectional"))
    )
    (net (code "74") (name "unconnected-(U1-COMP1_INP{slash}ADC1_IN16{slash}PB2-Pad15)") (class "Default")
      (node (ref "U1") (pin "15") (pinfunction "COMP1_INP/ADC1_IN16/PB2_15") (pintype "bidirectional"))
    )
    (net (code "75") (name "unconnected-(U2-FB{slash}NC-Pad15)") (class "Default")
      (node (ref "U2") (pin "15") (pinfunction "FB/NC_15") (pintype "bidirectional"))
    )
    (net (code "76") (name "unconnected-(U2-NC-Pad4)") (class "Default")
      (node (ref "U2") (pin "4") (pinfunction "NC_4") (pintype "no_connect"))
    )
    (net (code "77") (name "unconnected-(U2-NC-Pad8)") (class "Default")
      (node (ref "U2") (pin "8") (pinfunction "NC_8") (pintype "no_connect"))
    )
    (net (code "78") (name "unconnected-(U2-NC-Pad17)") (class "Default")
      (node (ref "U2") (pin "17") (pinfunction "NC_17") (pintype "no_connect"))
    )
    (net (code "79") (name "unconnected-(U2-NC-Pad18)") (class "Default")
      (node (ref "U2") (pin "18") (pinfunction "NC_18") (pintype "no_connect"))
    )
    (net (code "80") (name "unconnected-(X2-Pad19)") (class "Default")
      (node (ref "X2") (pin "19") (pinfunction "19_19") (pintype "passive"))
    )
    (net (code "81") (name "unconnected-(X5-Pad1)") (class "Default")
      (node (ref "X5") (pin "1") (pinfunction "1_1") (pintype "passive"))
    )
    (net (code "82") (name "unconnected-(X5-Pad3)") (class "Default")
      (node (ref "X5") (pin "3") (pinfunction "3_3") (pintype "passive"))
    )
    (net (code "83") (name "unconnected-(X5-Pad11)") (class "Default")
      (node (ref "X5") (pin "11") (pinfunction "11_11") (pintype "passive"))
    )
    (net (code "84") (name "unconnected-(X5-Pad13)") (class "Default")
      (node (ref "X5") (pin "13") (pinfunction "13_13") (pintype "passive"))
    )
  )
)
